# CURRENT_SENSE.net
KiCad netlist of a schematic drawn in Altium Designer
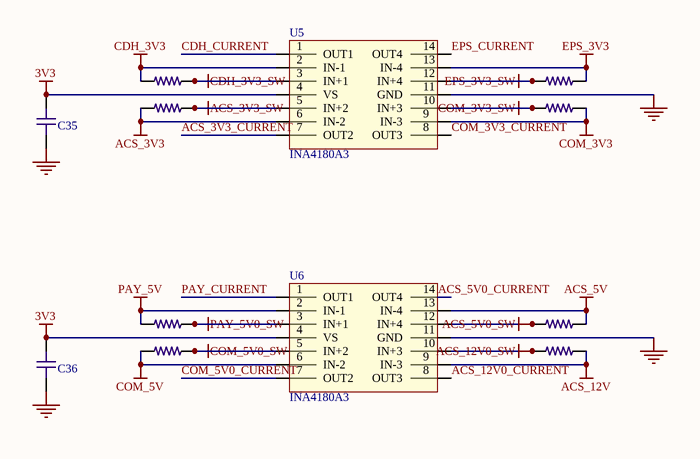
[diagram p0: CURRENT_SENSE.SchDoc]

(export (version "E")
  (design (tool "Eeschema 10.0.6"))
  (components
    (comp (ref "C35")
      (value "Capacitor")
      (footprint "C0603-IPC")
      (description "Chip Capacitor, 0603, 100nF, 10V, X7R")
      (libsource (lib "UBC_Orbit_Shared_Components") (part "Capacitor"))
    )
    (comp (ref "C36")
      (value "Capacitor")
      (footprint "C0603-IPC")
      (description "Chip Capacitor, 0603, 100nF, 10V, X7R")
      (libsource (lib "UBC_Orbit_Shared_Components") (part "Capacitor"))
    )
    (comp (ref "R16")
      (value "2512 Template")
      (footprint "R2512-IPC")
      (description "Chip Resistor, 2512, 30 mohms")
      (libsource (lib "Resistors") (part "2512 Template"))
    )
    (comp (ref "R17")
      (value "2512 Template")
      (footprint "R2512-IPC")
      (description "Chip Resistor, 2512, 30 mohms")
      (libsource (lib "Resistors") (part "2512 Template"))
    )
    (comp (ref "R18")
      (value "2512 Template")
      (footprint "R2512-IPC")
      (description "Chip Resistor, 2512, 30 mohms")
      (libsource (lib "Resistors") (part "2512 Template"))
    )
    (comp (ref "R19")
      (value "2512 Template")
      (footprint "R2512-IPC")
      (description "Chip Resistor, 2512, 30 mohms")
      (libsource (lib "Resistors") (part "2512 Template"))
    )
    (comp (ref "R20")
      (value "2512 Template")
      (footprint "R2512-IPC")
      (description "Chip Resistor, 2512, 30 mohms")
      (libsource (lib "Resistors") (part "2512 Template"))
    )
    (comp (ref "R21")
      (value "2512 Template")
      (footprint "R2512-IPC")
      (description "Chip Resistor, 2512, 30 mohms")
      (libsource (lib "Resistors") (part "2512 Template"))
    )
    (comp (ref "R22")
      (value "2512 Template")
      (footprint "R2512-IPC")
      (description "Chip Resistor, 2512, 30 mohms")
      (libsource (lib "Resistors") (part "2512 Template"))
    )
    (comp (ref "R23")
      (value "2512 Template")
      (footprint "R2512-IPC")
      (description "Chip Resistor, 2512, 30 mohms")
      (libsource (lib "Resistors") (part "2512 Template"))
    )
    (comp (ref "U5")
      (value "INA4180A3")
      (footprint "TSSOP14")
      (description "INA4180 4 channel current sense IC. A3(100 V/V)")
      (libsource (lib "Integrated_Circuits") (part "INA4180"))
    )
    (comp (ref "U6")
      (value "INA4180A3")
      (footprint "TSSOP14")
      (description "INA4180 4 channel current sense IC. A3(100 V/V)")
      (libsource (lib "Integrated_Circuits") (part "INA4180"))
    )
  )
  (nets
    (net (code "1") (name "/ACS_3V3_CURRENT") (class "Default")
      (node (ref "U5") (pin "7") (pinfunction "OUT2_7") (pintype "passive"))
    )
    (net (code "2") (name "/ACS_5V0_CURRENT") (class "Default")
      (node (ref "U6") (pin "14") (pinfunction "OUT4_14") (pintype "passive"))
    )
    (net (code "3") (name "/ACS_12V0_CURRENT") (class "Default")
      (node (ref "U6") (pin "8") (pinfunction "OUT3_8") (pintype "passive"))
    )
    (net (code "4") (name "/CDH_CURRENT") (class "Default")
      (node (ref "U5") (pin "1") (pinfunction "OUT1_1") (pintype "passive"))
    )
    (net (code "5") (name "/COM_3V3_CURRENT") (class "Default")
      (node (ref "U5") (pin "8") (pinfunction "OUT3_8") (pintype "passive"))
    )
    (net (code "6") (name "/COM_5V0_CURRENT") (class "Default")
      (node (ref "U6") (pin "7") (pinfunction "OUT2_7") (pintype "passive"))
    )
    (net (code "7") (name "/EPS_CURRENT") (class "Default")
      (node (ref "U5") (pin "14") (pinfunction "OUT4_14") (pintype "passive"))
    )
    (net (code "8") (name "/PAY_CURRENT") (class "Default")
      (node (ref "U6") (pin "1") (pinfunction "OUT1_1") (pintype "passive"))
    )
    (net (code "9") (name "3V3") (class "Default")
      (node (ref "C35") (pin "2") (pintype "passive"))
      (node (ref "C36") (pin "2") (pintype "passive"))
      (node (ref "U5") (pin "4") (pinfunction "VS_4") (pintype "passive"))
      (node (ref "U6") (pin "4") (pinfunction "VS_4") (pintype "passive"))
    )
    (net (code "10") (name "ACS_3V3") (class "Default")
      (node (ref "R18") (pin "1") (pintype "passive"))
      (node (ref "U5") (pin "6") (pinfunction "IN-2_6") (pintype "passive"))
    )
    (net (code "11") (name "ACS_3V3_SW") (class "Default")
      (node (ref "R18") (pin "2") (pintype "passive"))
      (node (ref "U5") (pin "5") (pinfunction "IN+2_5") (pintype "passive"))
    )
    (net (code "12") (name "ACS_5V") (class "Default")
      (node (ref "R21") (pin "2") (pintype "passive"))
      (node (ref "U6") (pin "13") (pinfunction "IN-4_13") (pintype "passive"))
    )
    (net (code "13") (name "ACS_5V0_SW") (class "Default")
      (node (ref "R21") (pin "1") (pintype "passive"))
      (node (ref "U6") (pin "12") (pinfunction "IN+4_12") (pintype "passive"))
    )
    (net (code "14") (name "ACS_12V") (class "Default")
      (node (ref "R23") (pin "2") (pintype "passive"))
      (node (ref "U6") (pin "9") (pinfunction "IN-3_9") (pintype "passive"))
    )
    (net (code "15") (name "ACS_12V0_SW") (class "Default")
      (node (ref "R23") (pin "1") (pintype "passive"))
      (node (ref "U6") (pin "10") (pinfunction "IN+3_10") (pintype "passive"))
    )
    (net (code "16") (name "CDH_3V3") (class "Default")
      (node (ref "R16") (pin "1") (pintype "passive"))
      (node (ref "U5") (pin "2") (pinfunction "IN-1_2") (pintype "passive"))
    )
    (net (code "17") (name "CDH_3V3_SW") (class "Default")
      (node (ref "R16") (pin "2") (pintype "passive"))
      (node (ref "U5") (pin "3") (pinfunction "IN+1_3") (pintype "passive"))
    )
    (net (code "18") (name "COM_3V3") (class "Default")
      (node (ref "R19") (pin "2") (pintype "passive"))
      (node (ref "U5") (pin "9") (pinfunction "IN-3_9") (pintype "passive"))
    )
    (net (code "19") (name "COM_3V3_SW") (class "Default")
      (node (ref "R19") (pin "1") (pintype "passive"))
      (node (ref "U5") (pin "10") (pinfunction "IN+3_10") (pintype "passive"))
    )
    (net (code "20") (name "COM_5V") (class "Default")
      (node (ref "R22") (pin "1") (pintype "passive"))
      (node (ref "U6") (pin "6") (pinfunction "IN-2_6") (pintype "passive"))
    )
    (net (code "21") (name "COM_5V0_SW") (class "Default")
      (node (ref "R22") (pin "2") (pintype "passive"))
      (node (ref "U6") (pin "5") (pinfunction "IN+2_5") (pintype "passive"))
    )
    (net (code "22") (name "EPS_3V3") (class "Default")
      (node (ref "R17") (pin "2") (pintype "passive"))
      (node (ref "U5") (pin "13") (pinfunction "IN-4_13") (pintype "passive"))
    )
    (net (code "23") (name "EPS_3V3_SW") (class "Default")
      (node (ref "R17") (pin "1") (pintype "passive"))
      (node (ref "U5") (pin "12") (pinfunction "IN+4_12") (pintype "passive"))
    )
    (net (code "24") (name "GND") (class "Default")
      (node (ref "C35") (pin "1") (pintype "passive"))
      (node (ref "C36") (pin "1") (pintype "passive"))
      (node (ref "U5") (pin "11") (pinfunction "GND_11") (pintype "passive"))
      (node (ref "U6") (pin "11") (pinfunction "GND_11") (pintype "passive"))
    )
    (net (code "25") (name "PAY_5V") (class "Default")
      (node (ref "R20") (pin "1") (pintype "passive"))
      (node (ref "U6") (pin "2") (pinfunction "IN-1_2") (pintype "passive"))
    )
    (net (code "26") (name "PAY_5V0_SW") (class "Default")
      (node (ref "R20") (pin "2") (pintype "passive"))
      (node (ref "U6") (pin "3") (pinfunction "IN+1_3") (pintype "passive"))
    )
  )
)
